# expander8.net
KiCad netlist of a schematic drawn in EAGLE
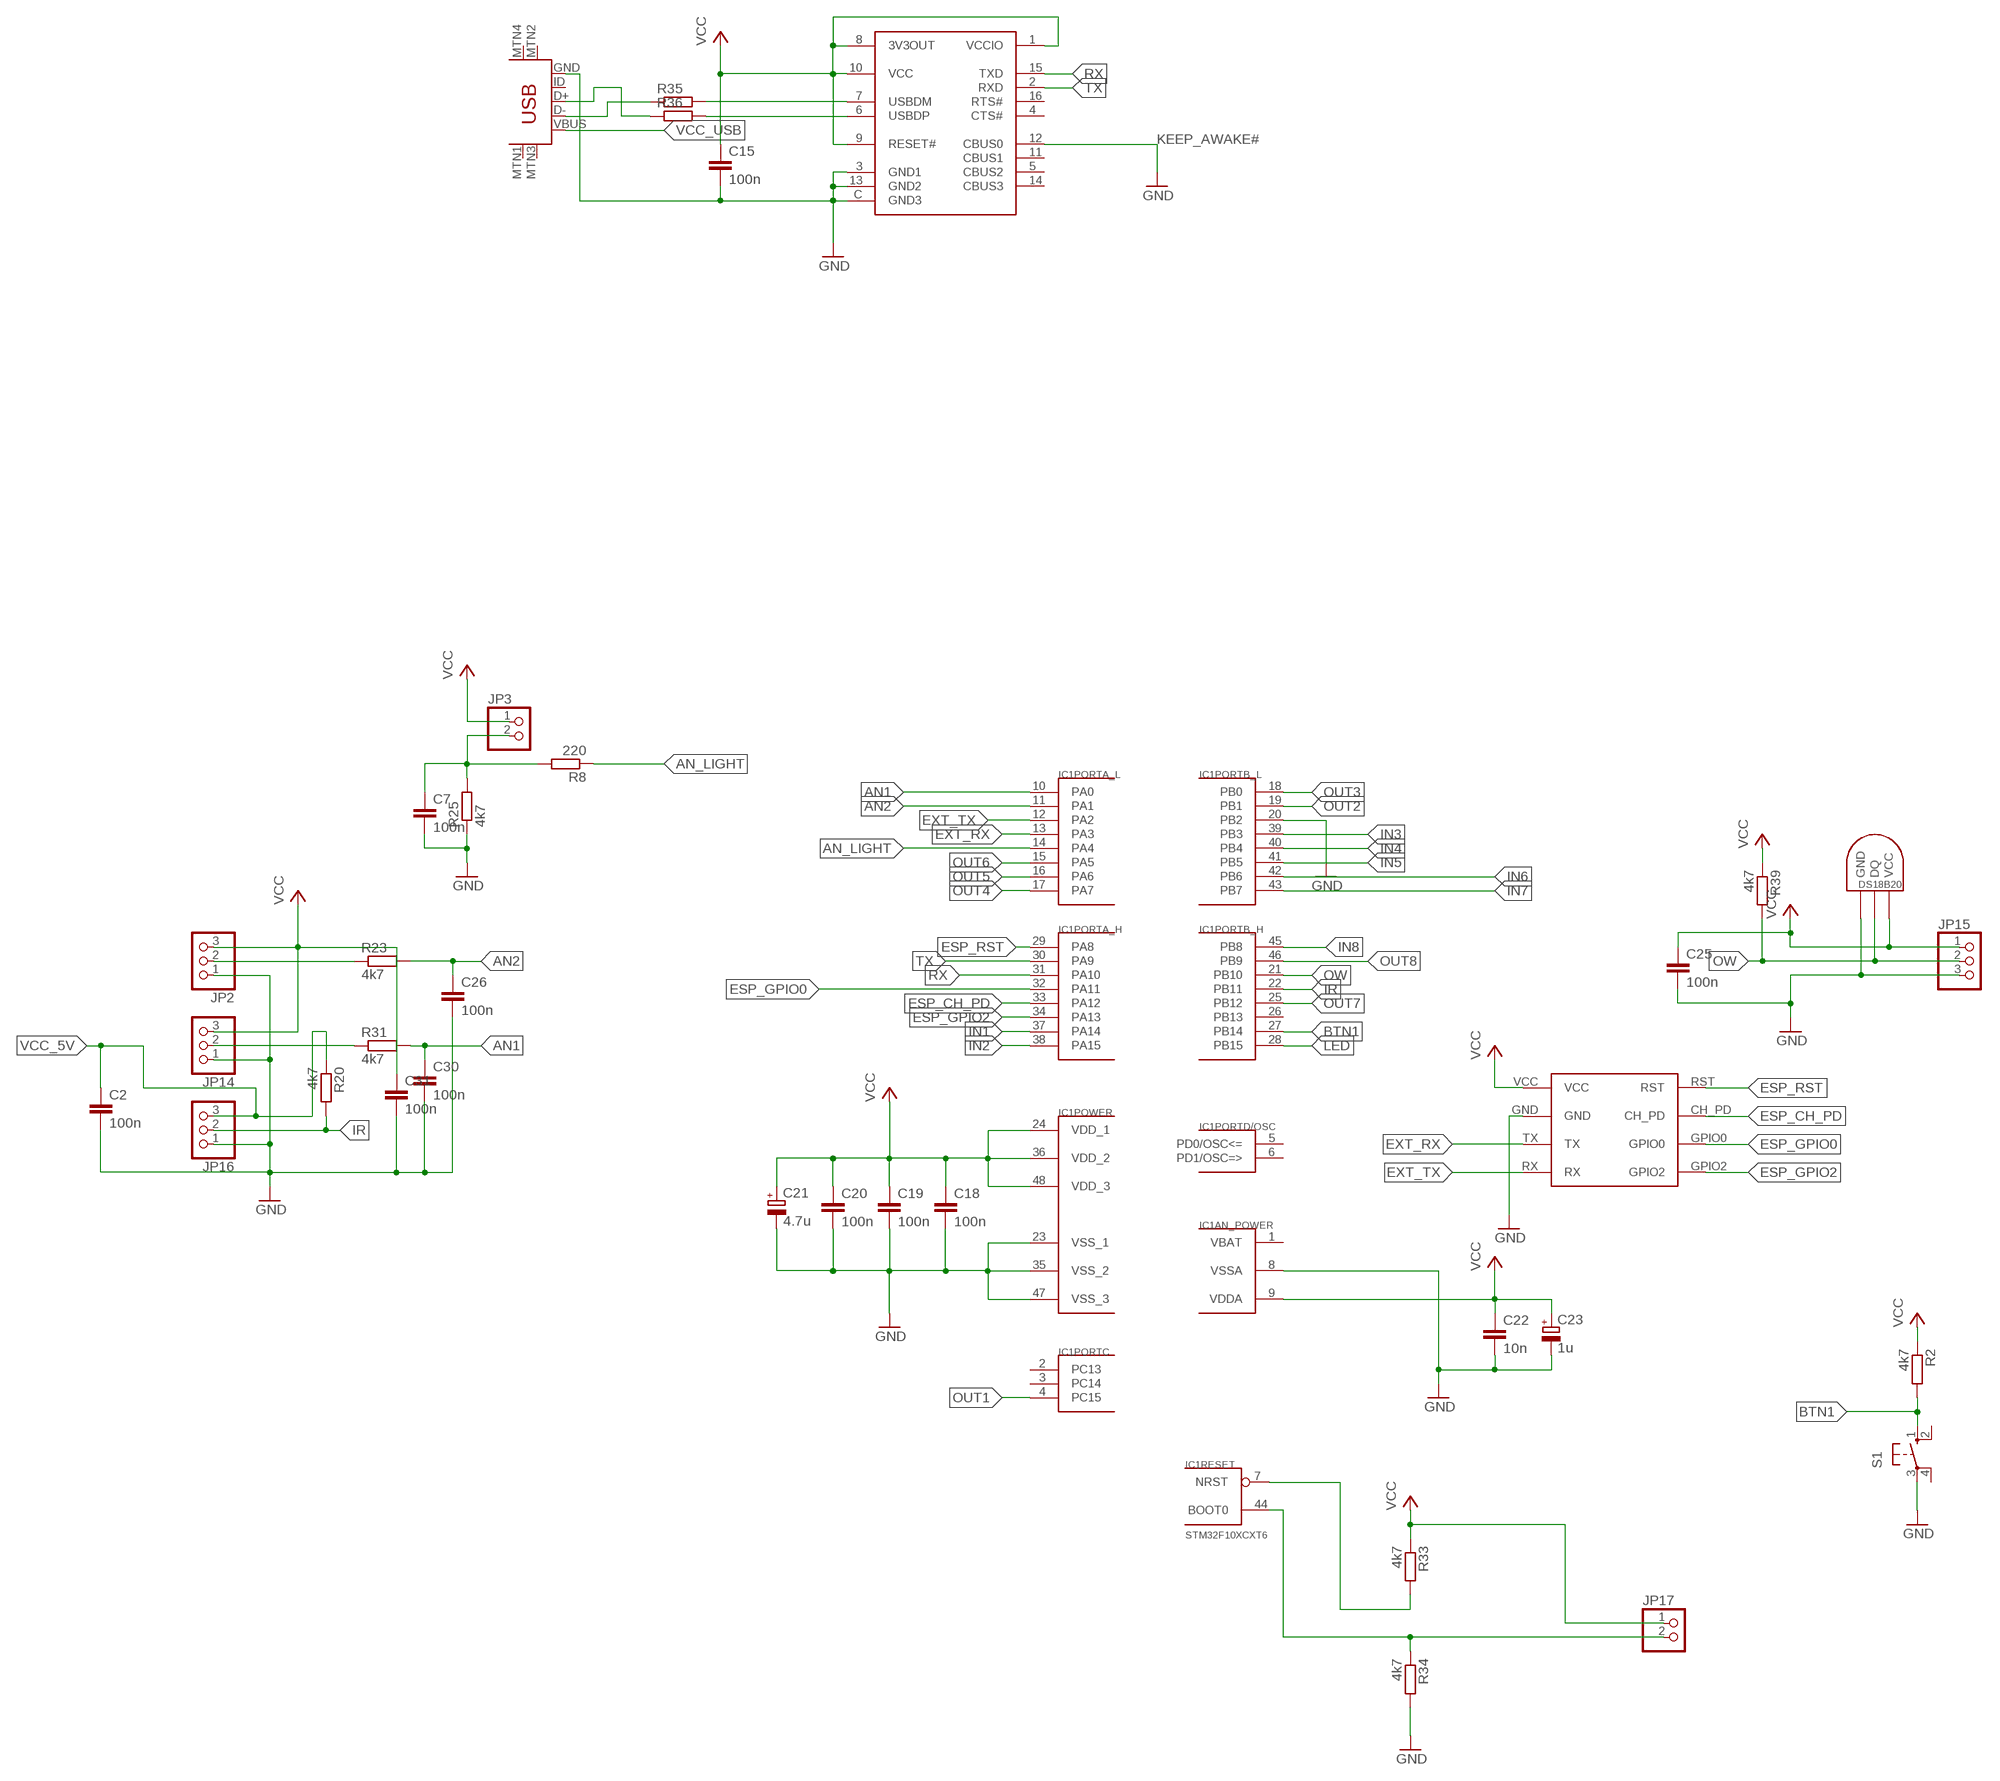
[diagram p0: schematic, sheet 1, part 1 of 3]
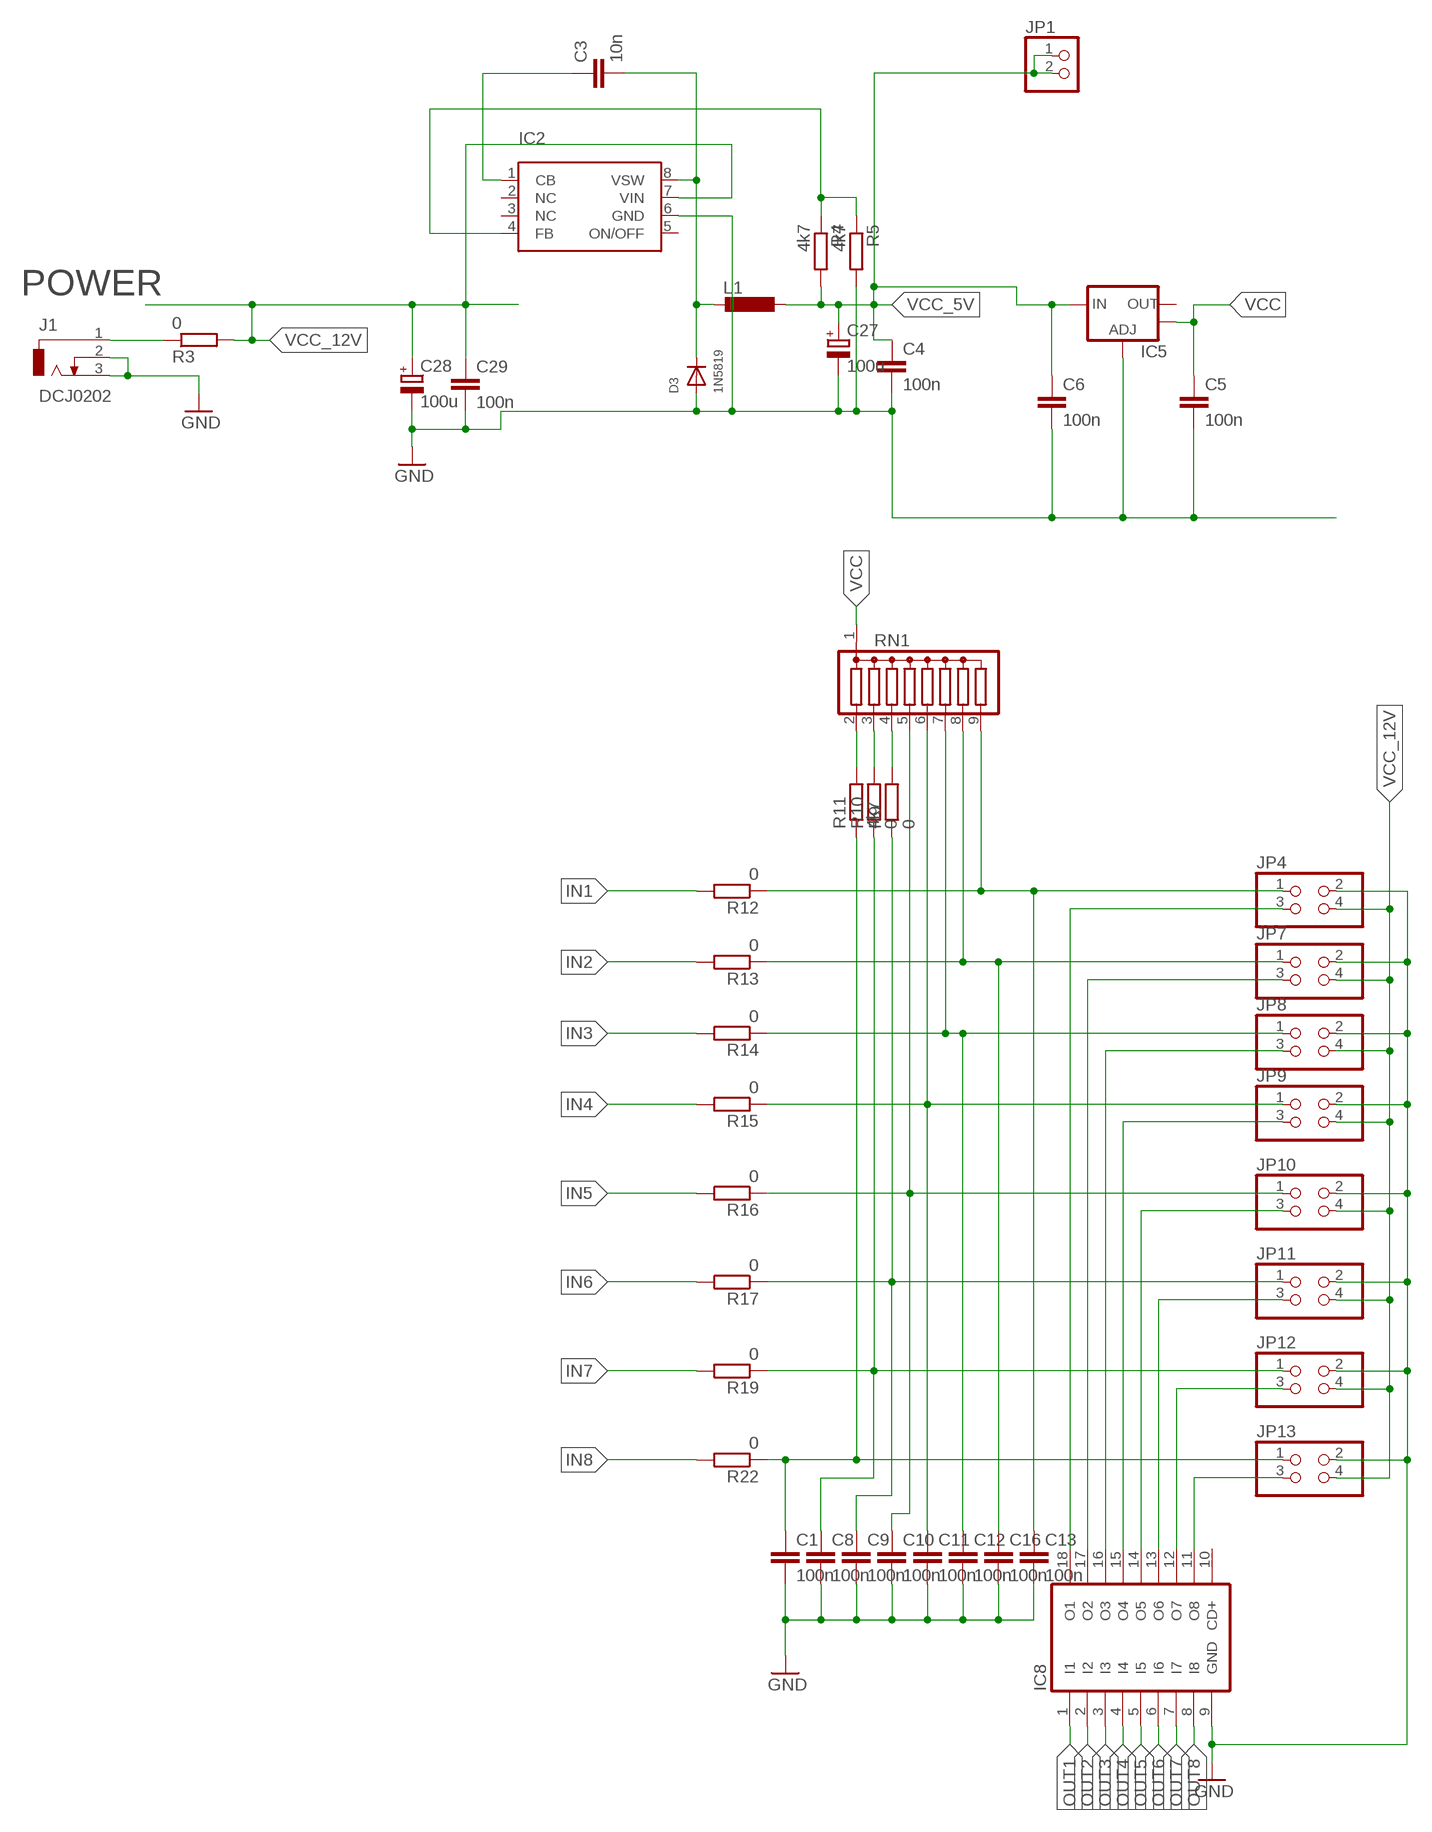
[diagram p1: schematic, sheet 1, part 2 of 3]
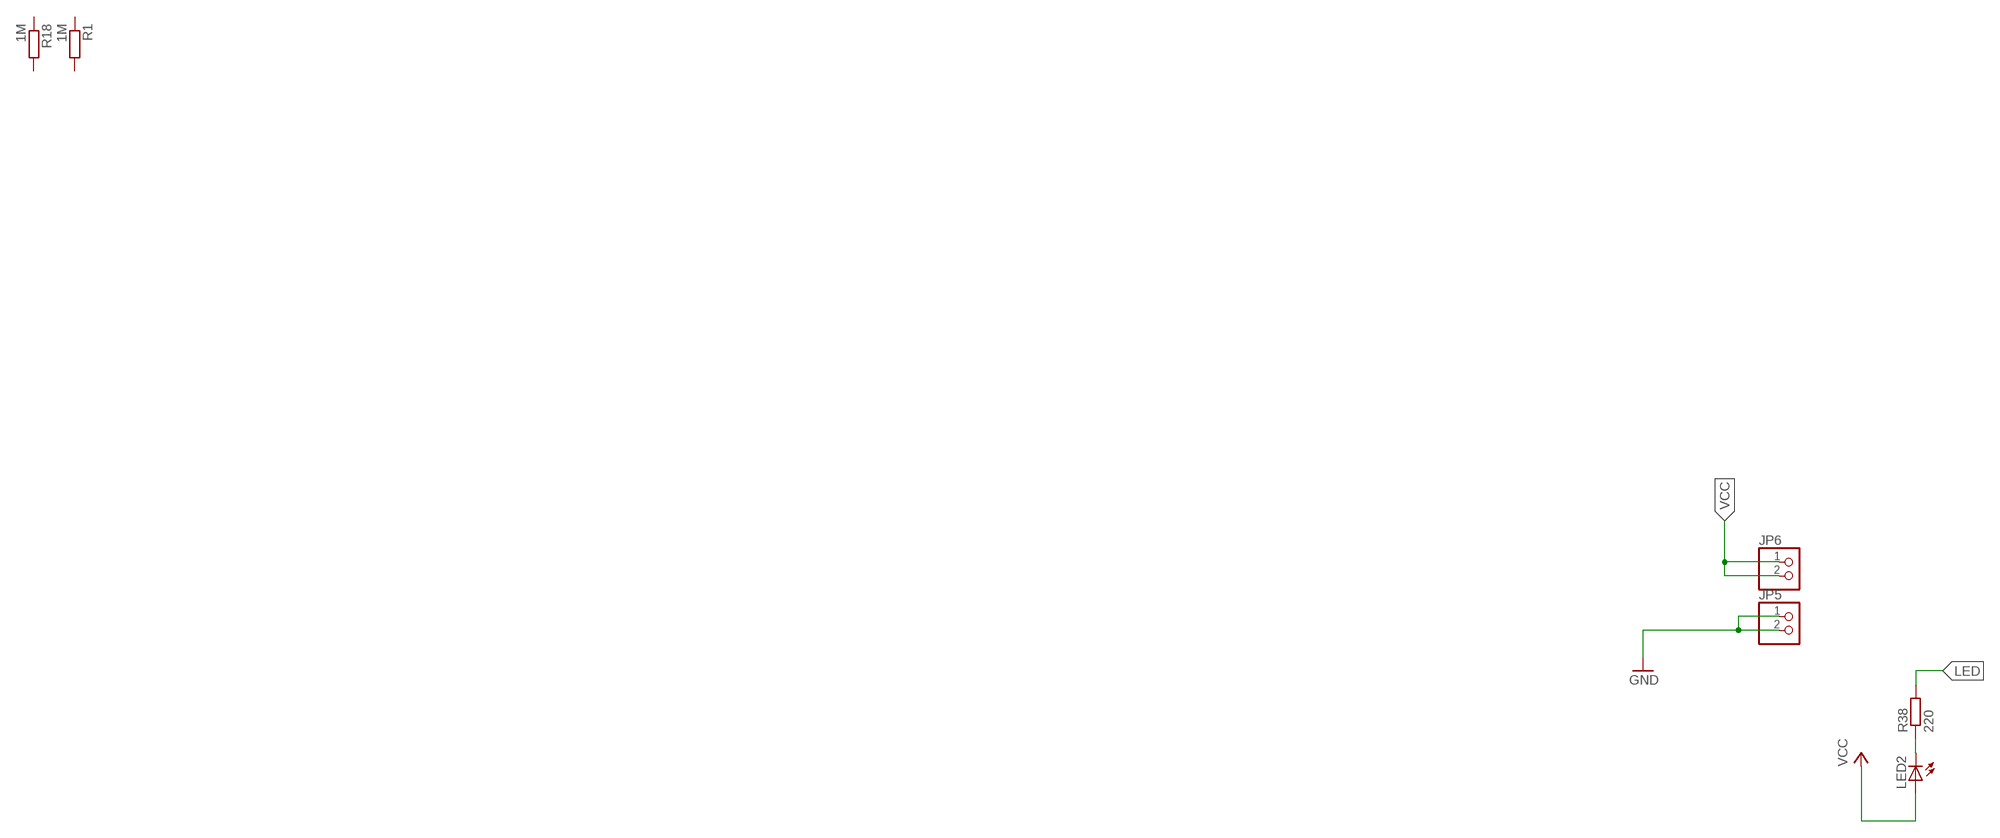
[diagram p2: schematic, sheet 1, part 3 of 3]

(export (version "E")
  (design (tool "Eeschema 10.0.6"))
  (components
    (comp (ref "C1")
      (value "100n")
      (footprint "eagle-import:C0805")
      (libsource (lib "eagle-import") (part "C-EUC0805"))
    )
    (comp (ref "C2")
      (value "100n")
      (footprint "eagle-import:C0805")
      (libsource (lib "eagle-import") (part "C-EUC0805"))
    )
    (comp (ref "C3")
      (value "10n")
      (footprint "eagle-import:C1206")
      (libsource (lib "eagle-import") (part "C-EUC1206"))
    )
    (comp (ref "C4")
      (value "100n")
      (footprint "eagle-import:C0805")
      (libsource (lib "eagle-import") (part "C-EUC0805"))
    )
    (comp (ref "C5")
      (value "100n")
      (footprint "eagle-import:C0805")
      (libsource (lib "eagle-import") (part "C-EUC0805"))
    )
    (comp (ref "C6")
      (value "100n")
      (footprint "eagle-import:C0805")
      (libsource (lib "eagle-import") (part "C-EUC0805"))
    )
    (comp (ref "C7")
      (value "100n")
      (footprint "eagle-import:C0805")
      (libsource (lib "eagle-import") (part "C-EUC0805"))
    )
    (comp (ref "C8")
      (value "100n")
      (footprint "eagle-import:C0805")
      (libsource (lib "eagle-import") (part "C-EUC0805"))
    )
    (comp (ref "C9")
      (value "100n")
      (footprint "eagle-import:C0805")
      (libsource (lib "eagle-import") (part "C-EUC0805"))
    )
    (comp (ref "C10")
      (value "100n")
      (footprint "eagle-import:C0805")
      (libsource (lib "eagle-import") (part "C-EUC0805"))
    )
    (comp (ref "C11")
      (value "100n")
      (footprint "eagle-import:C0805")
      (libsource (lib "eagle-import") (part "C-EUC0805"))
    )
    (comp (ref "C12")
      (value "100n")
      (footprint "eagle-import:C0805")
      (libsource (lib "eagle-import") (part "C-EUC0805"))
    )
    (comp (ref "C13")
      (value "100n")
      (footprint "eagle-import:C0805")
      (libsource (lib "eagle-import") (part "C-EUC0805"))
    )
    (comp (ref "C15")
      (value "100n")
      (footprint "eagle-import:C0805")
      (libsource (lib "eagle-import") (part "C-EUC0805"))
    )
    (comp (ref "C16")
      (value "100n")
      (footprint "eagle-import:C0805")
      (libsource (lib "eagle-import") (part "C-EUC0805"))
    )
    (comp (ref "C18")
      (value "100n")
      (footprint "eagle-import:C0805")
      (libsource (lib "eagle-import") (part "C-EUC0805"))
    )
    (comp (ref "C19")
      (value "100n")
      (footprint "eagle-import:C0805")
      (libsource (lib "eagle-import") (part "C-EUC0805"))
    )
    (comp (ref "C20")
      (value "100n")
      (footprint "eagle-import:C0805")
      (libsource (lib "eagle-import") (part "C-EUC0805"))
    )
    (comp (ref "C21")
      (value "4.7u")
      (footprint "eagle-import:E2,5-5")
      (libsource (lib "eagle-import") (part "CPOL-EUE2.5-5"))
    )
    (comp (ref "C22")
      (value "10n")
      (footprint "eagle-import:C0805")
      (libsource (lib "eagle-import") (part "C-EUC0805"))
    )
    (comp (ref "C23")
      (value "1u")
      (footprint "eagle-import:E2,5-5")
      (libsource (lib "eagle-import") (part "CPOL-EUE2.5-5"))
    )
    (comp (ref "C25")
      (value "100n")
      (footprint "eagle-import:C0805")
      (libsource (lib "eagle-import") (part "resistor_C-EUC0805"))
    )
    (comp (ref "C26")
      (value "100n")
      (footprint "eagle-import:C0805")
      (libsource (lib "eagle-import") (part "C-EUC0805"))
    )
    (comp (ref "C27")
      (value "100u")
      (footprint "eagle-import:E2,5-7")
      (libsource (lib "eagle-import") (part "CPOL-EUE2.5-7"))
    )
    (comp (ref "C28")
      (value "100u")
      (footprint "eagle-import:E2,5-7")
      (libsource (lib "eagle-import") (part "CPOL-EUE2.5-7"))
    )
    (comp (ref "C29")
      (value "100n")
      (footprint "eagle-import:C0805")
      (libsource (lib "eagle-import") (part "C-EUC0805"))
    )
    (comp (ref "C30")
      (value "100n")
      (footprint "eagle-import:C0805")
      (libsource (lib "eagle-import") (part "C-EUC0805"))
    )
    (comp (ref "C31")
      (value "100n")
      (footprint "eagle-import:C1206")
      (libsource (lib "eagle-import") (part "C-EUC1206"))
    )
    (comp (ref "D3")
      (value "1N5819")
      (footprint "eagle-import:SMADIODE")
      (libsource (lib "eagle-import") (part "DIODESMA"))
    )
    (comp (ref "IC1")
      (value "STM32F10XCXT6")
      (footprint "eagle-import:TQFP48")
      (libsource (lib "eagle-import") (part "STM32F10XCXT6"))
    )
    (comp (ref "IC2")
      (value "LM2674")
      (footprint "eagle-import:SO8")
      (libsource (lib "eagle-import") (part "LM2674"))
    )
    (comp (ref "IC5")
      (value "V_REG_LM1117SOT223")
      (footprint "eagle-import:SOT223")
      (libsource (lib "eagle-import") (part "V_REG_LM1117SOT223"))
    )
    (comp (ref "IC8")
      (value "ULN2803AD")
      (footprint "eagle-import:SO18W")
      (libsource (lib "eagle-import") (part "ULN2803AD"))
    )
    (comp (ref "J1")
      (value "DCJ0202")
      (footprint "eagle-import:DCJ0202")
      (libsource (lib "eagle-import") (part "DCJ0202"))
    )
    (comp (ref "JP1")
      (value "PINHD-1X2_2.54")
      (footprint "eagle-import:1X02")
      (libsource (lib "eagle-import") (part "PINHD-1X2_2.54"))
    )
    (comp (ref "JP2")
      (value "PINHD-1X3")
      (footprint "eagle-import:1X03")
      (libsource (lib "eagle-import") (part "PINHD-1X3"))
    )
    (comp (ref "JP3")
      (value "PINHD-1X2")
      (footprint "eagle-import:1X02")
      (libsource (lib "eagle-import") (part "PINHD-1X2"))
    )
    (comp (ref "JP4")
      (value "PINHD-2X2/90")
      (footprint "eagle-import:2X02_90")
      (libsource (lib "eagle-import") (part "PINHD-2X2/90"))
    )
    (comp (ref "JP5")
      (value "PINHD-1X2")
      (footprint "eagle-import:1X02")
      (libsource (lib "eagle-import") (part "PINHD-1X2"))
    )
    (comp (ref "JP6")
      (value "PINHD-1X2")
      (footprint "eagle-import:1X02")
      (libsource (lib "eagle-import") (part "PINHD-1X2"))
    )
    (comp (ref "JP7")
      (value "PINHD-2X2/90")
      (footprint "eagle-import:2X02_90")
      (libsource (lib "eagle-import") (part "PINHD-2X2/90"))
    )
    (comp (ref "JP8")
      (value "PINHD-2X2/90")
      (footprint "eagle-import:2X02_90")
      (libsource (lib "eagle-import") (part "PINHD-2X2/90"))
    )
    (comp (ref "JP9")
      (value "PINHD-2X2/90")
      (footprint "eagle-import:2X02_90")
      (libsource (lib "eagle-import") (part "PINHD-2X2/90"))
    )
    (comp (ref "JP10")
      (value "PINHD-2X2/90")
      (footprint "eagle-import:2X02_90")
      (libsource (lib "eagle-import") (part "PINHD-2X2/90"))
    )
    (comp (ref "JP11")
      (value "PINHD-2X2/90")
      (footprint "eagle-import:2X02_90")
      (libsource (lib "eagle-import") (part "PINHD-2X2/90"))
    )
    (comp (ref "JP12")
      (value "PINHD-2X2/90")
      (footprint "eagle-import:2X02_90")
      (libsource (lib "eagle-import") (part "PINHD-2X2/90"))
    )
    (comp (ref "JP13")
      (value "PINHD-2X2/90")
      (footprint "eagle-import:2X02_90")
      (libsource (lib "eagle-import") (part "PINHD-2X2/90"))
    )
    (comp (ref "JP14")
      (value "PINHD-1X3")
      (footprint "eagle-import:1X03")
      (libsource (lib "eagle-import") (part "PINHD-1X3"))
    )
    (comp (ref "JP15")
      (value "PINHD-1X3")
      (footprint "eagle-import:1X03")
      (libsource (lib "eagle-import") (part "PINHD-1X3"))
    )
    (comp (ref "JP16")
      (value "PINHD-1X3")
      (footprint "eagle-import:1X03")
      (libsource (lib "eagle-import") (part "PINHD-1X3"))
    )
    (comp (ref "JP17")
      (value "PINHD-1X2_2.54")
      (footprint "eagle-import:1X02")
      (libsource (lib "eagle-import") (part "PINHD-1X2_2.54"))
    )
    (comp (ref "L1")
      (value "L-EU0207/2V")
      (footprint "eagle-import:0207_2V")
      (libsource (lib "eagle-import") (part "L-EU0207/2V"))
    )
    (comp (ref "LED2")
      (value "LEDCHIPLED_0805")
      (footprint "eagle-import:CHIPLED_0805")
      (libsource (lib "eagle-import") (part "LEDCHIPLED_0805"))
    )
    (comp (ref "R1")
      (value "1M")
      (footprint "eagle-import:R1206")
      (libsource (lib "eagle-import") (part "rcl-kd_R-EU_R1206"))
    )
    (comp (ref "R2")
      (value "4k7")
      (footprint "eagle-import:R0805")
      (libsource (lib "eagle-import") (part "rcl-kd_R-EU_R0805"))
    )
    (comp (ref "R3")
      (value "0")
      (footprint "eagle-import:M1206")
      (libsource (lib "eagle-import") (part "R-EU_M1206"))
    )
    (comp (ref "R4")
      (value "4k7")
      (footprint "eagle-import:R0805")
      (libsource (lib "eagle-import") (part "resistor_R-EU_R0805"))
    )
    (comp (ref "R5")
      (value "4k7")
      (footprint "eagle-import:R0805")
      (libsource (lib "eagle-import") (part "resistor_R-EU_R0805"))
    )
    (comp (ref "R8")
      (value "220")
      (footprint "eagle-import:R1206")
      (libsource (lib "eagle-import") (part "resistor_R-EU_R1206"))
    )
    (comp (ref "R9")
      (value "0")
      (footprint "eagle-import:R0805")
      (libsource (lib "eagle-import") (part "resistor_R-EU_R0805"))
    )
    (comp (ref "R10")
      (value "0")
      (footprint "eagle-import:R0805")
      (libsource (lib "eagle-import") (part "resistor_R-EU_R0805"))
    )
    (comp (ref "R11")
      (value "4k7")
      (footprint "eagle-import:R0805")
      (libsource (lib "eagle-import") (part "resistor_R-EU_R0805"))
    )
    (comp (ref "R12")
      (value "0")
      (footprint "eagle-import:R0805")
      (libsource (lib "eagle-import") (part "resistor_R-EU_R0805"))
    )
    (comp (ref "R13")
      (value "0")
      (footprint "eagle-import:R0805")
      (libsource (lib "eagle-import") (part "resistor_R-EU_R0805"))
    )
    (comp (ref "R14")
      (value "0")
      (footprint "eagle-import:R0805")
      (libsource (lib "eagle-import") (part "resistor_R-EU_R0805"))
    )
    (comp (ref "R15")
      (value "0")
      (footprint "eagle-import:R0805")
      (libsource (lib "eagle-import") (part "resistor_R-EU_R0805"))
    )
    (comp (ref "R16")
      (value "0")
      (footprint "eagle-import:R0805")
      (libsource (lib "eagle-import") (part "resistor_R-EU_R0805"))
    )
    (comp (ref "R17")
      (value "0")
      (footprint "eagle-import:R0805")
      (libsource (lib "eagle-import") (part "resistor_R-EU_R0805"))
    )
    (comp (ref "R18")
      (value "1M")
      (footprint "eagle-import:R1206")
      (libsource (lib "eagle-import") (part "rcl-kd_R-EU_R1206"))
    )
    (comp (ref "R19")
      (value "0")
      (footprint "eagle-import:R0805")
      (libsource (lib "eagle-import") (part "resistor_R-EU_R0805"))
    )
    (comp (ref "R20")
      (value "4k7")
      (footprint "eagle-import:R0805")
      (libsource (lib "eagle-import") (part "resistor_R-EU_R0805"))
    )
    (comp (ref "R22")
      (value "0")
      (footprint "eagle-import:R0805")
      (libsource (lib "eagle-import") (part "resistor_R-EU_R0805"))
    )
    (comp (ref "R23")
      (value "4k7")
      (footprint "eagle-import:R0805")
      (libsource (lib "eagle-import") (part "resistor_R-EU_R0805"))
    )
    (comp (ref "R25")
      (value "4k7")
      (footprint "eagle-import:R0805")
      (libsource (lib "eagle-import") (part "resistor_R-EU_R0805"))
    )
    (comp (ref "R31")
      (value "4k7")
      (footprint "eagle-import:R1206")
      (libsource (lib "eagle-import") (part "resistor_R-EU_R1206"))
    )
    (comp (ref "R33")
      (value "4k7")
      (footprint "eagle-import:R0805")
      (libsource (lib "eagle-import") (part "rcl-kd_R-EU_R0805"))
    )
    (comp (ref "R34")
      (value "4k7")
      (footprint "eagle-import:R0805")
      (libsource (lib "eagle-import") (part "rcl-kd_R-EU_R0805"))
    )
    (comp (ref "R35")
      (value "R-EU_R1206")
      (footprint "eagle-import:R1206")
      (libsource (lib "eagle-import") (part "resistor_R-EU_R1206"))
    )
    (comp (ref "R36")
      (value "R-EU_R0805")
      (footprint "eagle-import:R0805")
      (libsource (lib "eagle-import") (part "resistor_R-EU_R0805"))
    )
    (comp (ref "R38")
      (value "220")
      (footprint "eagle-import:R0805")
      (libsource (lib "eagle-import") (part "resistor_R-EU_R0805"))
    )
    (comp (ref "R39")
      (value "4k7")
      (footprint "eagle-import:R0805")
      (libsource (lib "eagle-import") (part "resistor_R-EU_R0805"))
    )
    (comp (ref "RN1")
      (value "G08R")
      (footprint "eagle-import:SIL9")
      (libsource (lib "eagle-import") (part "G08R"))
    )
    (comp (ref "S1")
      (value "10-XX")
      (footprint "eagle-import:B3F-10XX")
      (fields (field (name "MPN") "B3F-1000"))
      (libsource (lib "eagle-import") (part "10-XX"))
    )
    (comp (ref "U$1")
      (value "ESP8266")
      (footprint "eagle-import:ESP8266")
      (libsource (lib "eagle-import") (part "ESP8266"))
    )
    (comp (ref "U$2")
      (value "USB-MINIB-5PIN")
      (footprint "eagle-import:USB-MINIB")
      (libsource (lib "eagle-import") (part "USB-MINIB-5PIN"))
    )
    (comp (ref "U$3")
      (value "FT230XQ")
      (footprint "eagle-import:FT230XQ")
      (libsource (lib "eagle-import") (part "FT230XQ"))
    )
    (comp (ref "U$4")
      (value "DS1820TO92")
      (footprint "eagle-import:DS1820")
      (libsource (lib "eagle-import") (part "DS1820TO92"))
    )
  )
  (nets
    (net (code "1") (name "/VBAT") (class "Default")
      (node (ref "IC1") (pin "1") (pinfunction "VBAT_1") (pintype "power_in"))
    )
    (net (code "2") (name "AN1") (class "Default")
      (node (ref "C30") (pin "1") (pinfunction "1_1") (pintype "passive"))
      (node (ref "IC1") (pin "10") (pinfunction "PA0_10") (pintype "bidirectional"))
      (node (ref "R31") (pin "2") (pinfunction "2_2") (pintype "passive"))
    )
    (net (code "3") (name "AN2") (class "Default")
      (node (ref "C26") (pin "1") (pinfunction "1_1") (pintype "passive"))
      (node (ref "IC1") (pin "11") (pinfunction "PA1_11") (pintype "bidirectional"))
      (node (ref "R23") (pin "2") (pinfunction "2_2") (pintype "passive"))
    )
    (net (code "4") (name "AN_LIGHT") (class "Default")
      (node (ref "IC1") (pin "14") (pinfunction "PA4_14") (pintype "bidirectional"))
      (node (ref "R8") (pin "1") (pinfunction "1_1") (pintype "passive"))
    )
    (net (code "5") (name "BTN1") (class "Default")
      (node (ref "IC1") (pin "27") (pinfunction "PB14_27") (pintype "bidirectional"))
      (node (ref "R2") (pin "2") (pinfunction "2_2") (pintype "passive"))
      (node (ref "S1") (pin "1") (pinfunction "S_1") (pintype "passive"))
    )
    (net (code "6") (name "ESP_CH_PD") (class "Default")
      (node (ref "IC1") (pin "33") (pinfunction "PA12_33") (pintype "bidirectional"))
      (node (ref "U$1") (pin "CH_PD") (pinfunction "CH_PD_CH_PD") (pintype "bidirectional"))
    )
    (net (code "7") (name "ESP_GPIO0") (class "Default")
      (node (ref "IC1") (pin "32") (pinfunction "PA11_32") (pintype "bidirectional"))
      (node (ref "U$1") (pin "GPIO0") (pinfunction "GPIO0_GPIO0") (pintype "bidirectional"))
    )
    (net (code "8") (name "ESP_GPIO2") (class "Default")
      (node (ref "IC1") (pin "34") (pinfunction "PA13_34") (pintype "bidirectional"))
      (node (ref "U$1") (pin "GPIO2") (pinfunction "GPIO2_GPIO2") (pintype "bidirectional"))
    )
    (net (code "9") (name "ESP_RST") (class "Default")
      (node (ref "IC1") (pin "29") (pinfunction "PA8_29") (pintype "bidirectional"))
      (node (ref "U$1") (pin "RST") (pinfunction "RST_RST") (pintype "bidirectional"))
    )
    (net (code "10") (name "EXT_RX") (class "Default")
      (node (ref "IC1") (pin "13") (pinfunction "PA3_13") (pintype "bidirectional"))
      (node (ref "U$1") (pin "TX") (pinfunction "TX_TX") (pintype "bidirectional"))
    )
    (net (code "11") (name "EXT_TX") (class "Default")
      (node (ref "IC1") (pin "12") (pinfunction "PA2_12") (pintype "bidirectional"))
      (node (ref "U$1") (pin "RX") (pinfunction "RX_RX") (pintype "bidirectional"))
    )
    (net (code "12") (name "GND") (class "Default")
      (node (ref "C1") (pin "2") (pinfunction "2_2") (pintype "passive"))
      (node (ref "C10") (pin "2") (pinfunction "2_2") (pintype "passive"))
      (node (ref "C11") (pin "2") (pinfunction "2_2") (pintype "passive"))
      (node (ref "C12") (pin "2") (pinfunction "2_2") (pintype "passive"))
      (node (ref "C13") (pin "2") (pinfunction "2_2") (pintype "passive"))
      (node (ref "C15") (pin "2") (pinfunction "2_2") (pintype "passive"))
      (node (ref "C16") (pin "2") (pinfunction "2_2") (pintype "passive"))
      (node (ref "C18") (pin "2") (pinfunction "2_2") (pintype "passive"))
      (node (ref "C19") (pin "2") (pinfunction "2_2") (pintype "passive"))
      (node (ref "C2") (pin "2") (pinfunction "2_2") (pintype "passive"))
      (node (ref "C20") (pin "2") (pinfunction "2_2") (pintype "passive"))
      (node (ref "C21") (pin "-") (pinfunction "-_-") (pintype "passive"))
      (node (ref "C22") (pin "2") (pinfunction "2_2") (pintype "passive"))
      (node (ref "C23") (pin "-") (pinfunction "-_-") (pintype "passive"))
      (node (ref "C25") (pin "2") (pinfunction "2_2") (pintype "passive"))
      (node (ref "C26") (pin "2") (pinfunction "2_2") (pintype "passive"))
      (node (ref "C27") (pin "-") (pinfunction "-_-") (pintype "passive"))
      (node (ref "C28") (pin "-") (pinfunction "-_-") (pintype "passive"))
      (node (ref "C29") (pin "2") (pinfunction "2_2") (pintype "passive"))
      (node (ref "C30") (pin "2") (pinfunction "2_2") (pintype "passive"))
      (node (ref "C31") (pin "2") (pinfunction "2_2") (pintype "passive"))
      (node (ref "C4") (pin "2") (pinfunction "2_2") (pintype "passive"))
      (node (ref "C5") (pin "2") (pinfunction "2_2") (pintype "passive"))
      (node (ref "C6") (pin "2") (pinfunction "2_2") (pintype "passive"))
      (node (ref "C7") (pin "2") (pinfunction "2_2") (pintype "passive"))
      (node (ref "C8") (pin "2") (pinfunction "2_2") (pintype "passive"))
      (node (ref "C9") (pin "2") (pinfunction "2_2") (pintype "passive"))
      (node (ref "D3") (pin "A") (pinfunction "A_A") (pintype "passive"))
      (node (ref "IC1") (pin "20") (pinfunction "PB2_20") (pintype "bidirectional"))
      (node (ref "IC1") (pin "23") (pinfunction "VSS_1_23") (pintype "power_in"))
      (node (ref "IC1") (pin "35") (pinfunction "VSS_2_35") (pintype "power_in"))
      (node (ref "IC1") (pin "47") (pinfunction "VSS_3_47") (pintype "power_in"))
      (node (ref "IC1") (pin "8") (pinfunction "VSSA_8") (pintype "power_in"))
      (node (ref "IC2") (pin "6") (pinfunction "GND_6") (pintype "bidirectional"))
      (node (ref "IC5") (pin "1") (pinfunction "ADJ_1") (pintype "input"))
      (node (ref "IC8") (pin "9") (pinfunction "GND_9") (pintype "power_in"))
      (node (ref "J1") (pin "2") (pinfunction "2_2") (pintype "passive"))
      (node (ref "J1") (pin "3") (pinfunction "3_3") (pintype "passive"))
      (node (ref "JP10") (pin "2") (pinfunction "2_2") (pintype "passive"))
      (node (ref "JP11") (pin "2") (pinfunction "2_2") (pintype "passive"))
      (node (ref "JP12") (pin "2") (pinfunction "2_2") (pintype "passive"))
      (node (ref "JP13") (pin "2") (pinfunction "2_2") (pintype "passive"))
      (node (ref "JP14") (pin "1") (pinfunction "1_1") (pintype "passive"))
      (node (ref "JP15") (pin "3") (pinfunction "3_3") (pintype "passive"))
      (node (ref "JP16") (pin "1") (pinfunction "1_1") (pintype "passive"))
      (node (ref "JP2") (pin "1") (pinfunction "1_1") (pintype "passive"))
      (node (ref "JP4") (pin "2") (pinfunction "2_2") (pintype "passive"))
      (node (ref "JP5") (pin "1") (pinfunction "1_1") (pintype "passive"))
      (node (ref "JP5") (pin "2") (pinfunction "2_2") (pintype "passive"))
      (node (ref "JP7") (pin "2") (pinfunction "2_2") (pintype "passive"))
      (node (ref "JP8") (pin "2") (pinfunction "2_2") (pintype "passive"))
      (node (ref "JP9") (pin "2") (pinfunction "2_2") (pintype "passive"))
      (node (ref "R25") (pin "1") (pinfunction "1_1") (pintype "passive"))
      (node (ref "R34") (pin "2") (pinfunction "2_2") (pintype "passive"))
      (node (ref "R5") (pin "2") (pinfunction "2_2") (pintype "passive"))
      (node (ref "S1") (pin "3") (pinfunction "P_3") (pintype "passive"))
      (node (ref "U$1") (pin "GND") (pinfunction "GND_GND") (pintype "bidirectional"))
      (node (ref "U$2") (pin "GND") (pinfunction "GND_GND") (pintype "bidirectional"))
      (node (ref "U$3") (pin "12") (pinfunction "CBUS0_12") (pintype "bidirectional"))
      (node (ref "U$3") (pin "13") (pinfunction "GND2_13") (pintype "bidirectional"))
      (node (ref "U$3") (pin "3") (pinfunction "GND1_3") (pintype "bidirectional"))
      (node (ref "U$3") (pin "C") (pinfunction "GND3_C") (pintype "bidirectional"))
      (node (ref "U$4") (pin "GND") (pinfunction "GND_GND") (pintype "power_in"))
    )
    (net (code "13") (name "IN1") (class "Default")
      (node (ref "IC1") (pin "37") (pinfunction "PA14_37") (pintype "bidirectional"))
      (node (ref "R12") (pin "2") (pinfunction "2_2") (pintype "passive"))
    )
    (net (code "14") (name "IN2") (class "Default")
      (node (ref "IC1") (pin "38") (pinfunction "PA15_38") (pintype "bidirectional"))
      (node (ref "R13") (pin "2") (pinfunction "2_2") (pintype "passive"))
    )
    (net (code "15") (name "IN3") (class "Default")
      (node (ref "IC1") (pin "39") (pinfunction "PB3_39") (pintype "bidirectional"))
      (node (ref "R14") (pin "2") (pinfunction "2_2") (pintype "passive"))
    )
    (net (code "16") (name "IN4") (class "Default")
      (node (ref "IC1") (pin "40") (pinfunction "PB4_40") (pintype "bidirectional"))
      (node (ref "R15") (pin "2") (pinfunction "2_2") (pintype "passive"))
    )
    (net (code "17") (name "IN5") (class "Default")
      (node (ref "IC1") (pin "41") (pinfunction "PB5_41") (pintype "bidirectional"))
      (node (ref "R16") (pin "2") (pinfunction "2_2") (pintype "passive"))
    )
    (net (code "18") (name "IN6") (class "Default")
      (node (ref "IC1") (pin "42") (pinfunction "PB6_42") (pintype "bidirectional"))
      (node (ref "R17") (pin "2") (pinfunction "2_2") (pintype "passive"))
    )
    (net (code "19") (name "IN7") (class "Default")
      (node (ref "IC1") (pin "43") (pinfunction "PB7_43") (pintype "bidirectional"))
      (node (ref "R19") (pin "2") (pinfunction "2_2") (pintype "passive"))
    )
    (net (code "20") (name "IN8") (class "Default")
      (node (ref "IC1") (pin "45") (pinfunction "PB8_45") (pintype "bidirectional"))
      (node (ref "R22") (pin "2") (pinfunction "2_2") (pintype "passive"))
    )
    (net (code "21") (name "IR") (class "Default")
      (node (ref "IC1") (pin "22") (pinfunction "PB11_22") (pintype "bidirectional"))
      (node (ref "JP16") (pin "2") (pinfunction "2_2") (pintype "passive"))
      (node (ref "R20") (pin "2") (pinfunction "2_2") (pintype "passive"))
    )
    (net (code "22") (name "LED") (class "Default")
      (node (ref "IC1") (pin "28") (pinfunction "PB15_28") (pintype "bidirectional"))
      (node (ref "R38") (pin "2") (pinfunction "2_2") (pintype "passive"))
    )
    (net (code "23") (name "Net-(C1-Pad1)") (class "Default")
      (node (ref "C1") (pin "1") (pinfunction "1_1") (pintype "passive"))
      (node (ref "JP13") (pin "1") (pinfunction "1_1") (pintype "passive"))
      (node (ref "R11") (pin "1") (pinfunction "1_1") (pintype "passive"))
      (node (ref "R22") (pin "1") (pinfunction "1_1") (pintype "passive"))
    )
    (net (code "24") (name "Net-(C7-Pad1)") (class "Default")
      (node (ref "C7") (pin "1") (pinfunction "1_1") (pintype "passive"))
      (node (ref "JP3") (pin "2") (pinfunction "2_2") (pintype "passive"))
      (node (ref "R25") (pin "2") (pinfunction "2_2") (pintype "passive"))
      (node (ref "R8") (pin "2") (pinfunction "2_2") (pintype "passive"))
    )
    (net (code "25") (name "Net-(C8-Pad1)") (class "Default")
      (node (ref "C8") (pin "1") (pinfunction "1_1") (pintype "passive"))
      (node (ref "JP12") (pin "1") (pinfunction "1_1") (pintype "passive"))
      (node (ref "R10") (pin "1") (pinfunction "1_1") (pintype "passive"))
      (node (ref "R19") (pin "1") (pinfunction "1_1") (pintype "passive"))
    )
    (net (code "26") (name "Net-(C9-Pad1)") (class "Default")
      (node (ref "C9") (pin "1") (pinfunction "1_1") (pintype "passive"))
      (node (ref "JP11") (pin "1") (pinfunction "1_1") (pintype "passive"))
      (node (ref "R17") (pin "1") (pinfunction "1_1") (pintype "passive"))
      (node (ref "R9") (pin "1") (pinfunction "1_1") (pintype "passive"))
    )
    (net (code "27") (name "Net-(C10-Pad1)") (class "Default")
      (node (ref "C10") (pin "1") (pinfunction "1_1") (pintype "passive"))
      (node (ref "JP10") (pin "1") (pinfunction "1_1") (pintype "passive"))
      (node (ref "R16") (pin "1") (pinfunction "1_1") (pintype "passive"))
      (node (ref "RN1") (pin "5") (pinfunction "5_5") (pintype "passive"))
    )
    (net (code "28") (name "Net-(C11-Pad1)") (class "Default")
      (node (ref "C11") (pin "1") (pinfunction "1_1") (pintype "passive"))
      (node (ref "JP9") (pin "1") (pinfunction "1_1") (pintype "passive"))
      (node (ref "R15") (pin "1") (pinfunction "1_1") (pintype "passive"))
      (node (ref "RN1") (pin "6") (pinfunction "6_6") (pintype "passive"))
    )
    (net (code "29") (name "Net-(C12-Pad1)") (class "Default")
      (node (ref "C12") (pin "1") (pinfunction "1_1") (pintype "passive"))
      (node (ref "JP8") (pin "1") (pinfunction "1_1") (pintype "passive"))
      (node (ref "R14") (pin "1") (pinfunction "1_1") (pintype "passive"))
      (node (ref "RN1") (pin "7") (pinfunction "7_7") (pintype "passive"))
    )
    (net (code "30") (name "Net-(C13-Pad1)") (class "Default")
      (node (ref "C13") (pin "1") (pinfunction "1_1") (pintype "passive"))
      (node (ref "JP4") (pin "1") (pinfunction "1_1") (pintype "passive"))
      (node (ref "R12") (pin "1") (pinfunction "1_1") (pintype "passive"))
      (node (ref "RN1") (pin "9") (pinfunction "9_9") (pintype "passive"))
    )
    (net (code "31") (name "Net-(C16-Pad1)") (class "Default")
      (node (ref "C16") (pin "1") (pinfunction "1_1") (pintype "passive"))
      (node (ref "JP7") (pin "1") (pinfunction "1_1") (pintype "passive"))
      (node (ref "R13") (pin "1") (pinfunction "1_1") (pintype "passive"))
      (node (ref "RN1") (pin "8") (pinfunction "8_8") (pintype "passive"))
    )
    (net (code "32") (name "Net-(IC1I-BOOT0)") (class "Default")
      (node (ref "IC1") (pin "44") (pinfunction "BOOT0_44") (pintype "input"))
      (node (ref "JP17") (pin "2") (pinfunction "2_2") (pintype "passive"))
      (node (ref "R34") (pin "1") (pinfunction "1_1") (pintype "passive"))
    )
    (net (code "33") (name "Net-(IC1I-NRST)") (class "Default")
      (node (ref "IC1") (pin "7") (pinfunction "NRST_7") (pintype "input"))
      (node (ref "R33") (pin "2") (pinfunction "2_2") (pintype "passive"))
    )
    (net (code "34") (name "Net-(IC2-CB)") (class "Default")
      (node (ref "C3") (pin "1") (pinfunction "1_1") (pintype "passive"))
      (node (ref "IC2") (pin "1") (pinfunction "CB_1") (pintype "bidirectional"))
    )
    (net (code "35") (name "Net-(IC2-FB)") (class "Default")
      (node (ref "IC2") (pin "4") (pinfunction "FB_4") (pintype "bidirectional"))
      (node (ref "R4") (pin "1") (pinfunction "1_1") (pintype "passive"))
      (node (ref "R5") (pin "1") (pinfunction "1_1") (pintype "passive"))
    )
    (net (code "36") (name "Net-(IC2-VSW)") (class "Default")
      (node (ref "C3") (pin "2") (pinfunction "2_2") (pintype "passive"))
      (node (ref "D3") (pin "C") (pinfunction "C_C") (pintype "passive"))
      (node (ref "IC2") (pin "8") (pinfunction "VSW_8") (pintype "bidirectional"))
      (node (ref "L1") (pin "2") (pinfunction "2_2") (pintype "passive"))
    )
    (net (code "37") (name "Net-(IC8-O1)") (class "Default")
      (node (ref "IC8") (pin "18") (pinfunction "O1_18") (pintype "open_collector"))
      (node (ref "JP4") (pin "3") (pinfunction "3_3") (pintype "passive"))
    )
    (net (code "38") (name "Net-(IC8-O2)") (class "Default")
      (node (ref "IC8") (pin "17") (pinfunction "O2_17") (pintype "open_collector"))
      (node (ref "JP7") (pin "3") (pinfunction "3_3") (pintype "passive"))
    )
    (net (code "39") (name "Net-(IC8-O3)") (class "Default")
      (node (ref "IC8") (pin "16") (pinfunction "O3_16") (pintype "open_collector"))
      (node (ref "JP8") (pin "3") (pinfunction "3_3") (pintype "passive"))
    )
    (net (code "40") (name "Net-(IC8-O4)") (class "Default")
      (node (ref "IC8") (pin "15") (pinfunction "O4_15") (pintype "open_collector"))
      (node (ref "JP9") (pin "3") (pinfunction "3_3") (pintype "passive"))
    )
    (net (code "41") (name "Net-(IC8-O5)") (class "Default")
      (node (ref "IC8") (pin "14") (pinfunction "O5_14") (pintype "open_collector"))
      (node (ref "JP10") (pin "3") (pinfunction "3_3") (pintype "passive"))
    )
    (net (code "42") (name "Net-(IC8-O6)") (class "Default")
      (node (ref "IC8") (pin "13") (pinfunction "O6_13") (pintype "open_collector"))
      (node (ref "JP11") (pin "3") (pinfunction "3_3") (pintype "passive"))
    )
    (net (code "43") (name "Net-(IC8-O7)") (class "Default")
      (node (ref "IC8") (pin "12") (pinfunction "O7_12") (pintype "open_collector"))
      (node (ref "JP12") (pin "3") (pinfunction "3_3") (pintype "passive"))
    )
    (net (code "44") (name "Net-(IC8-O8)") (class "Default")
      (node (ref "IC8") (pin "11") (pinfunction "O8_11") (pintype "open_collector"))
      (node (ref "JP13") (pin "3") (pinfunction "3_3") (pintype "passive"))
    )
    (net (code "45") (name "Net-(J1-Pad1)") (class "Default")
      (node (ref "J1") (pin "1") (pinfunction "1_1") (pintype "passive"))
      (node (ref "R3") (pin "1") (pinfunction "1_1") (pintype "passive"))
    )
    (net (code "46") (name "Net-(JP2-Pad2)") (class "Default")
      (node (ref "JP2") (pin "2") (pinfunction "2_2") (pintype "passive"))
      (node (ref "R23") (pin "1") (pinfunction "1_1") (pintype "passive"))
    )
    (net (code "47") (name "Net-(JP14-Pad2)") (class "Default")
      (node (ref "JP14") (pin "2") (pinfunction "2_2") (pintype "passive"))
      (node (ref "R31") (pin "1") (pinfunction "1_1") (pintype "passive"))
    )
    (net (code "48") (name "Net-(LED2-PadC)") (class "Default")
      (node (ref "LED2") (pin "C") (pinfunction "C_C") (pintype "passive"))
      (node (ref "R38") (pin "1") (pinfunction "1_1") (pintype "passive"))
    )
    (net (code "49") (name "Net-(R9-Pad2)") (class "Default")
      (node (ref "R9") (pin "2") (pinfunction "2_2") (pintype "passive"))
      (node (ref "RN1") (pin "4") (pinfunction "4_4") (pintype "passive"))
    )
    (net (code "50") (name "Net-(R10-Pad2)") (class "Default")
      (node (ref "R10") (pin "2") (pinfunction "2_2") (pintype "passive"))
      (node (ref "RN1") (pin "3") (pinfunction "3_3") (pintype "passive"))
    )
    (net (code "51") (name "Net-(R11-Pad2)") (class "Default")
      (node (ref "R11") (pin "2") (pinfunction "2_2") (pintype "passive"))
      (node (ref "RN1") (pin "2") (pinfunction "2_2") (pintype "passive"))
    )
    (net (code "52") (name "Net-(R35-Pad1)") (class "Default")
      (node (ref "R35") (pin "1") (pinfunction "1_1") (pintype "passive"))
      (node (ref "U$2") (pin "D-") (pinfunction "D-_D-") (pintype "bidirectional"))
    )
    (net (code "53") (name "Net-(R36-Pad1)") (class "Default")
      (node (ref "R36") (pin "1") (pinfunction "1_1") (pintype "passive"))
      (node (ref "U$2") (pin "D+") (pinfunction "D+_D+") (pintype "bidirectional"))
    )
    (net (code "54") (name "Net-(U$3-USBDM)") (class "Default")
      (node (ref "R35") (pin "2") (pinfunction "2_2") (pintype "passive"))
      (node (ref "U$3") (pin "7") (pinfunction "USBDM_7") (pintype "bidirectional"))
    )
    (net (code "55") (name "Net-(U$3-USBDP)") (class "Default")
      (node (ref "R36") (pin "2") (pinfunction "2_2") (pintype "passive"))
      (node (ref "U$3") (pin "6") (pinfunction "USBDP_6") (pintype "bidirectional"))
    )
    (net (code "56") (name "OUT1") (class "Default")
      (node (ref "IC1") (pin "4") (pinfunction "PC15_4") (pintype "bidirectional"))
      (node (ref "IC8") (pin "1") (pinfunction "I1_1") (pintype "input"))
    )
    (net (code "57") (name "OUT2") (class "Default")
      (node (ref "IC1") (pin "19") (pinfunction "PB1_19") (pintype "bidirectional"))
      (node (ref "IC8") (pin "2") (pinfunction "I2_2") (pintype "input"))
    )
    (net (code "58") (name "OUT3") (class "Default")
      (node (ref "IC1") (pin "18") (pinfunction "PB0_18") (pintype "bidirectional"))
      (node (ref "IC8") (pin "3") (pinfunction "I3_3") (pintype "input"))
    )
    (net (code "59") (name "OUT4") (class "Default")
      (node (ref "IC1") (pin "17") (pinfunction "PA7_17") (pintype "bidirectional"))
      (node (ref "IC8") (pin "4") (pinfunction "I4_4") (pintype "input"))
    )
    (net (code "60") (name "OUT5") (class "Default")
      (node (ref "IC1") (pin "16") (pinfunction "PA6_16") (pintype "bidirectional"))
      (node (ref "IC8") (pin "5") (pinfunction "I5_5") (pintype "input"))
    )
    (net (code "61") (name "OUT6") (class "Default")
      (node (ref "IC1") (pin "15") (pinfunction "PA5_15") (pintype "bidirectional"))
      (node (ref "IC8") (pin "6") (pinfunction "I6_6") (pintype "input"))
    )
    (net (code "62") (name "OUT7") (class "Default")
      (node (ref "IC1") (pin "25") (pinfunction "PB12_25") (pintype "bidirectional"))
      (node (ref "IC8") (pin "7") (pinfunction "I7_7") (pintype "input"))
    )
    (net (code "63") (name "OUT8") (class "Default")
      (node (ref "IC1") (pin "46") (pinfunction "PB9_46") (pintype "bidirectional"))
      (node (ref "IC8") (pin "8") (pinfunction "I8_8") (pintype "input"))
    )
    (net (code "64") (name "OW") (class "Default")
      (node (ref "IC1") (pin "21") (pinfunction "PB10_21") (pintype "bidirectional"))
      (node (ref "JP15") (pin "2") (pinfunction "2_2") (pintype "passive"))
      (node (ref "R39") (pin "2") (pinfunction "2_2") (pintype "passive"))
      (node (ref "U$4") (pin "DQ") (pinfunction "DQ_DQ") (pintype "bidirectional"))
    )
    (net (code "65") (name "RX") (class "Default")
      (node (ref "IC1") (pin "31") (pinfunction "PA10_31") (pintype "bidirectional"))
      (node (ref "U$3") (pin "15") (pinfunction "TXD_15") (pintype "bidirectional"))
    )
    (net (code "66") (name "TX") (class "Default")
      (node (ref "IC1") (pin "30") (pinfunction "PA9_30") (pintype "bidirectional"))
      (node (ref "U$3") (pin "2") (pinfunction "RXD_2") (pintype "bidirectional"))
    )
    (net (code "67") (name "VCC") (class "Default")
      (node (ref "C15") (pin "1") (pinfunction "1_1") (pintype "passive"))
      (node (ref "C18") (pin "1") (pinfunction "1_1") (pintype "passive"))
      (node (ref "C19") (pin "1") (pinfunction "1_1") (pintype "passive"))
      (node (ref "C20") (pin "1") (pinfunction "1_1") (pintype "passive"))
      (node (ref "C21") (pin "+") (pinfunction "+_+") (pintype "passive"))
      (node (ref "C22") (pin "1") (pinfunction "1_1") (pintype "passive"))
      (node (ref "C23") (pin "+") (pinfunction "+_+") (pintype "passive"))
      (node (ref "C25") (pin "1") (pinfunction "1_1") (pintype "passive"))
      (node (ref "C31") (pin "1") (pinfunction "1_1") (pintype "passive"))
      (node (ref "C5") (pin "1") (pinfunction "1_1") (pintype "passive"))
      (node (ref "IC1") (pin "24") (pinfunction "VDD_1_24") (pintype "power_in"))
      (node (ref "IC1") (pin "36") (pinfunction "VDD_2_36") (pintype "power_in"))
      (node (ref "IC1") (pin "48") (pinfunction "VDD_3_48") (pintype "power_in"))
      (node (ref "IC1") (pin "9") (pinfunction "VDDA_9") (pintype "power_in"))
      (node (ref "IC5") (pin "4") (pinfunction "OUT_4") (pintype "output"))
      (node (ref "JP14") (pin "3") (pinfunction "3_3") (pintype "passive"))
      (node (ref "JP15") (pin "1") (pinfunction "1_1") (pintype "passive"))
      (node (ref "JP17") (pin "1") (pinfunction "1_1") (pintype "passive"))
      (node (ref "JP2") (pin "3") (pinfunction "3_3") (pintype "passive"))
      (node (ref "JP3") (pin "1") (pinfunction "1_1") (pintype "passive"))
      (node (ref "JP6") (pin "1") (pinfunction "1_1") (pintype "passive"))
      (node (ref "JP6") (pin "2") (pinfunction "2_2") (pintype "passive"))
      (node (ref "LED2") (pin "A") (pinfunction "A_A") (pintype "passive"))
      (node (ref "R2") (pin "1") (pinfunction "1_1") (pintype "passive"))
      (node (ref "R33") (pin "1") (pinfunction "1_1") (pintype "passive"))
      (node (ref "R39") (pin "1") (pinfunction "1_1") (pintype "passive"))
      (node (ref "RN1") (pin "1") (pinfunction "1_1") (pintype "passive"))
      (node (ref "U$1") (pin "VCC") (pinfunction "VCC_VCC") (pintype "bidirectional"))
      (node (ref "U$3") (pin "1") (pinfunction "VCCIO_1") (pintype "bidirectional"))
      (node (ref "U$3") (pin "10") (pinfunction "VCC_10") (pintype "bidirectional"))
      (node (ref "U$3") (pin "8") (pinfunction "3V3OUT_8") (pintype "bidirectional"))
      (node (ref "U$3") (pin "9") (pinfunction "RESET#_9") (pintype "bidirectional"))
      (node (ref "U$4") (pin "VDD") (pinfunction "VCC_VDD") (pintype "power_in"))
    )
    (net (code "68") (name "VCC_5V") (class "Default")
      (node (ref "C2") (pin "1") (pinfunction "1_1") (pintype "passive"))
      (node (ref "C27") (pin "+") (pinfunction "+_+") (pintype "passive"))
      (node (ref "C4") (pin "1") (pinfunction "1_1") (pintype "passive"))
      (node (ref "C6") (pin "1") (pinfunction "1_1") (pintype "passive"))
      (node (ref "IC5") (pin "3") (pinfunction "IN_3") (pintype "input"))
      (node (ref "JP1") (pin "1") (pinfunction "1_1") (pintype "passive"))
      (node (ref "JP1") (pin "2") (pinfunction "2_2") (pintype "passive"))
      (node (ref "JP16") (pin "3") (pinfunction "3_3") (pintype "passive"))
      (node (ref "L1") (pin "1") (pinfunction "1_1") (pintype "passive"))
      (node (ref "R20") (pin "1") (pinfunction "1_1") (pintype "passive"))
      (node (ref "R4") (pin "2") (pinfunction "2_2") (pintype "passive"))
    )
    (net (code "69") (name "VCC_12V") (class "Default")
      (node (ref "C28") (pin "+") (pinfunction "+_+") (pintype "passive"))
      (node (ref "C29") (pin "1") (pinfunction "1_1") (pintype "passive"))
      (node (ref "IC2") (pin "7") (pinfunction "VIN_7") (pintype "bidirectional"))
      (node (ref "JP10") (pin "4") (pinfunction "4_4") (pintype "passive"))
      (node (ref "JP11") (pin "4") (pinfunction "4_4") (pintype "passive"))
      (node (ref "JP12") (pin "4") (pinfunction "4_4") (pintype "passive"))
      (node (ref "JP13") (pin "4") (pinfunction "4_4") (pintype "passive"))
      (node (ref "JP4") (pin "4") (pinfunction "4_4") (pintype "passive"))
      (node (ref "JP7") (pin "4") (pinfunction "4_4") (pintype "passive"))
      (node (ref "JP8") (pin "4") (pinfunction "4_4") (pintype "passive"))
      (node (ref "JP9") (pin "4") (pinfunction "4_4") (pintype "passive"))
      (node (ref "R3") (pin "2") (pinfunction "2_2") (pintype "passive"))
    )
    (net (code "70") (name "VCC_USB") (class "Default")
      (node (ref "U$2") (pin "VBUS") (pinfunction "VBUS_VBUS") (pintype "bidirectional"))
    )
    (net (code "71") (name "unconnected-(IC1D-PB13-Pad26)") (class "Default")
      (node (ref "IC1") (pin "26") (pinfunction "PB13_26") (pintype "bidirectional"))
    )
    (net (code "72") (name "unconnected-(IC1F-PC13-Pad2)") (class "Default")
      (node (ref "IC1") (pin "2") (pinfunction "PC13_2") (pintype "bidirectional"))
    )
    (net (code "73") (name "unconnected-(IC1F-PC14-Pad3)") (class "Default")
      (node (ref "IC1") (pin "3") (pinfunction "PC14_3") (pintype "bidirectional"))
    )
    (net (code "74") (name "unconnected-(IC1G-PD0{slash}OSC<=-Pad5)") (class "Default")
      (node (ref "IC1") (pin "5") (pinfunction "PD0/OSC<=_5") (pintype "bidirectional"))
    )
    (net (code "75") (name "unconnected-(IC1G-PD1{slash}OSC=>-Pad6)") (class "Default")
      (node (ref "IC1") (pin "6") (pinfunction "PD1/OSC=>_6") (pintype "bidirectional"))
    )
    (net (code "76") (name "unconnected-(IC2-NC-Pad2)") (class "Default")
      (node (ref "IC2") (pin "2") (pinfunction "NC_2") (pintype "no_connect"))
    )
    (net (code "77") (name "unconnected-(IC2-NC-Pad3)") (class "Default")
      (node (ref "IC2") (pin "3") (pinfunction "NC_3") (pintype "no_connect"))
    )
    (net (code "78") (name "unconnected-(IC2-ON{slash}OFF-Pad5)") (class "Default")
      (node (ref "IC2") (pin "5") (pinfunction "ON/OFF_5") (pintype "bidirectional"))
    )
    (net (code "79") (name "unconnected-(IC5-OUT-Pad2)") (class "Default")
      (node (ref "IC5") (pin "2") (pinfunction "OUT_2") (pintype "output"))
    )
    (net (code "80") (name "unconnected-(IC8-CD+-Pad10)") (class "Default")
      (node (ref "IC8") (pin "10") (pinfunction "CD+_10") (pintype "passive"))
    )
    (net (code "81") (name "unconnected-(R1-Pad1)") (class "Default")
      (node (ref "R1") (pin "1") (pinfunction "1_1") (pintype "passive"))
    )
    (net (code "82") (name "unconnected-(R1-Pad2)") (class "Default")
      (node (ref "R1") (pin "2") (pinfunction "2_2") (pintype "passive"))
    )
    (net (code "83") (name "unconnected-(R18-Pad1)") (class "Default")
      (node (ref "R18") (pin "1") (pinfunction "1_1") (pintype "passive"))
    )
    (net (code "84") (name "unconnected-(R18-Pad2)") (class "Default")
      (node (ref "R18") (pin "2") (pinfunction "2_2") (pintype "passive"))
    )
    (net (code "85") (name "unconnected-(S1-P1-Pad4)") (class "Default")
      (node (ref "S1") (pin "4") (pinfunction "P1_4") (pintype "passive"))
    )
    (net (code "86") (name "unconnected-(S1-S1-Pad2)") (class "Default")
      (node (ref "S1") (pin "2") (pinfunction "S1_2") (pintype "passive"))
    )
    (net (code "87") (name "unconnected-(U$2-MTN1-PadMTN3)") (class "Default")
      (node (ref "U$2") (pin "MTN3") (pinfunction "MTN1_MTN3") (pintype "bidirectional"))
    )
    (net (code "88") (name "unconnected-(U$2-MTN2-PadMTN1)") (class "Default")
      (node (ref "U$2") (pin "MTN1") (pinfunction "MTN2_MTN1") (pintype "bidirectional"))
    )
    (net (code "89") (name "unconnected-(U$2-MTN3-PadMTN2)") (class "Default")
      (node (ref "U$2") (pin "MTN2") (pinfunction "MTN3_MTN2") (pintype "bidirectional"))
    )
    (net (code "90") (name "unconnected-(U$2-PadID)") (class "Default")
      (node (ref "U$2") (pin "ID") (pinfunction "ID_ID") (pintype "bidirectional"))
    )
    (net (code "91") (name "unconnected-(U$2-PadMTN4)") (class "Default")
      (node (ref "U$2") (pin "MTN4") (pinfunction "MTN4_MTN4") (pintype "bidirectional"))
    )
    (net (code "92") (name "unconnected-(U$3-CBUS1-Pad11)") (class "Default")
      (node (ref "U$3") (pin "11") (pinfunction "CBUS1_11") (pintype "bidirectional"))
    )
    (net (code "93") (name "unconnected-(U$3-CBUS2-Pad5)") (class "Default")
      (node (ref "U$3") (pin "5") (pinfunction "CBUS2_5") (pintype "bidirectional"))
    )
    (net (code "94") (name "unconnected-(U$3-CBUS3-Pad14)") (class "Default")
      (node (ref "U$3") (pin "14") (pinfunction "CBUS3_14") (pintype "bidirectional"))
    )
    (net (code "95") (name "unconnected-(U$3-CTS#-Pad4)") (class "Default")
      (node (ref "U$3") (pin "4") (pinfunction "CTS#_4") (pintype "bidirectional"))
    )
    (net (code "96") (name "unconnected-(U$3-RTS#-Pad16)") (class "Default")
      (node (ref "U$3") (pin "16") (pinfunction "RTS#_16") (pintype "bidirectional"))
    )
  )
)
